# ThermoActuator.net
KiCad netlist of a schematic drawn in EAGLE
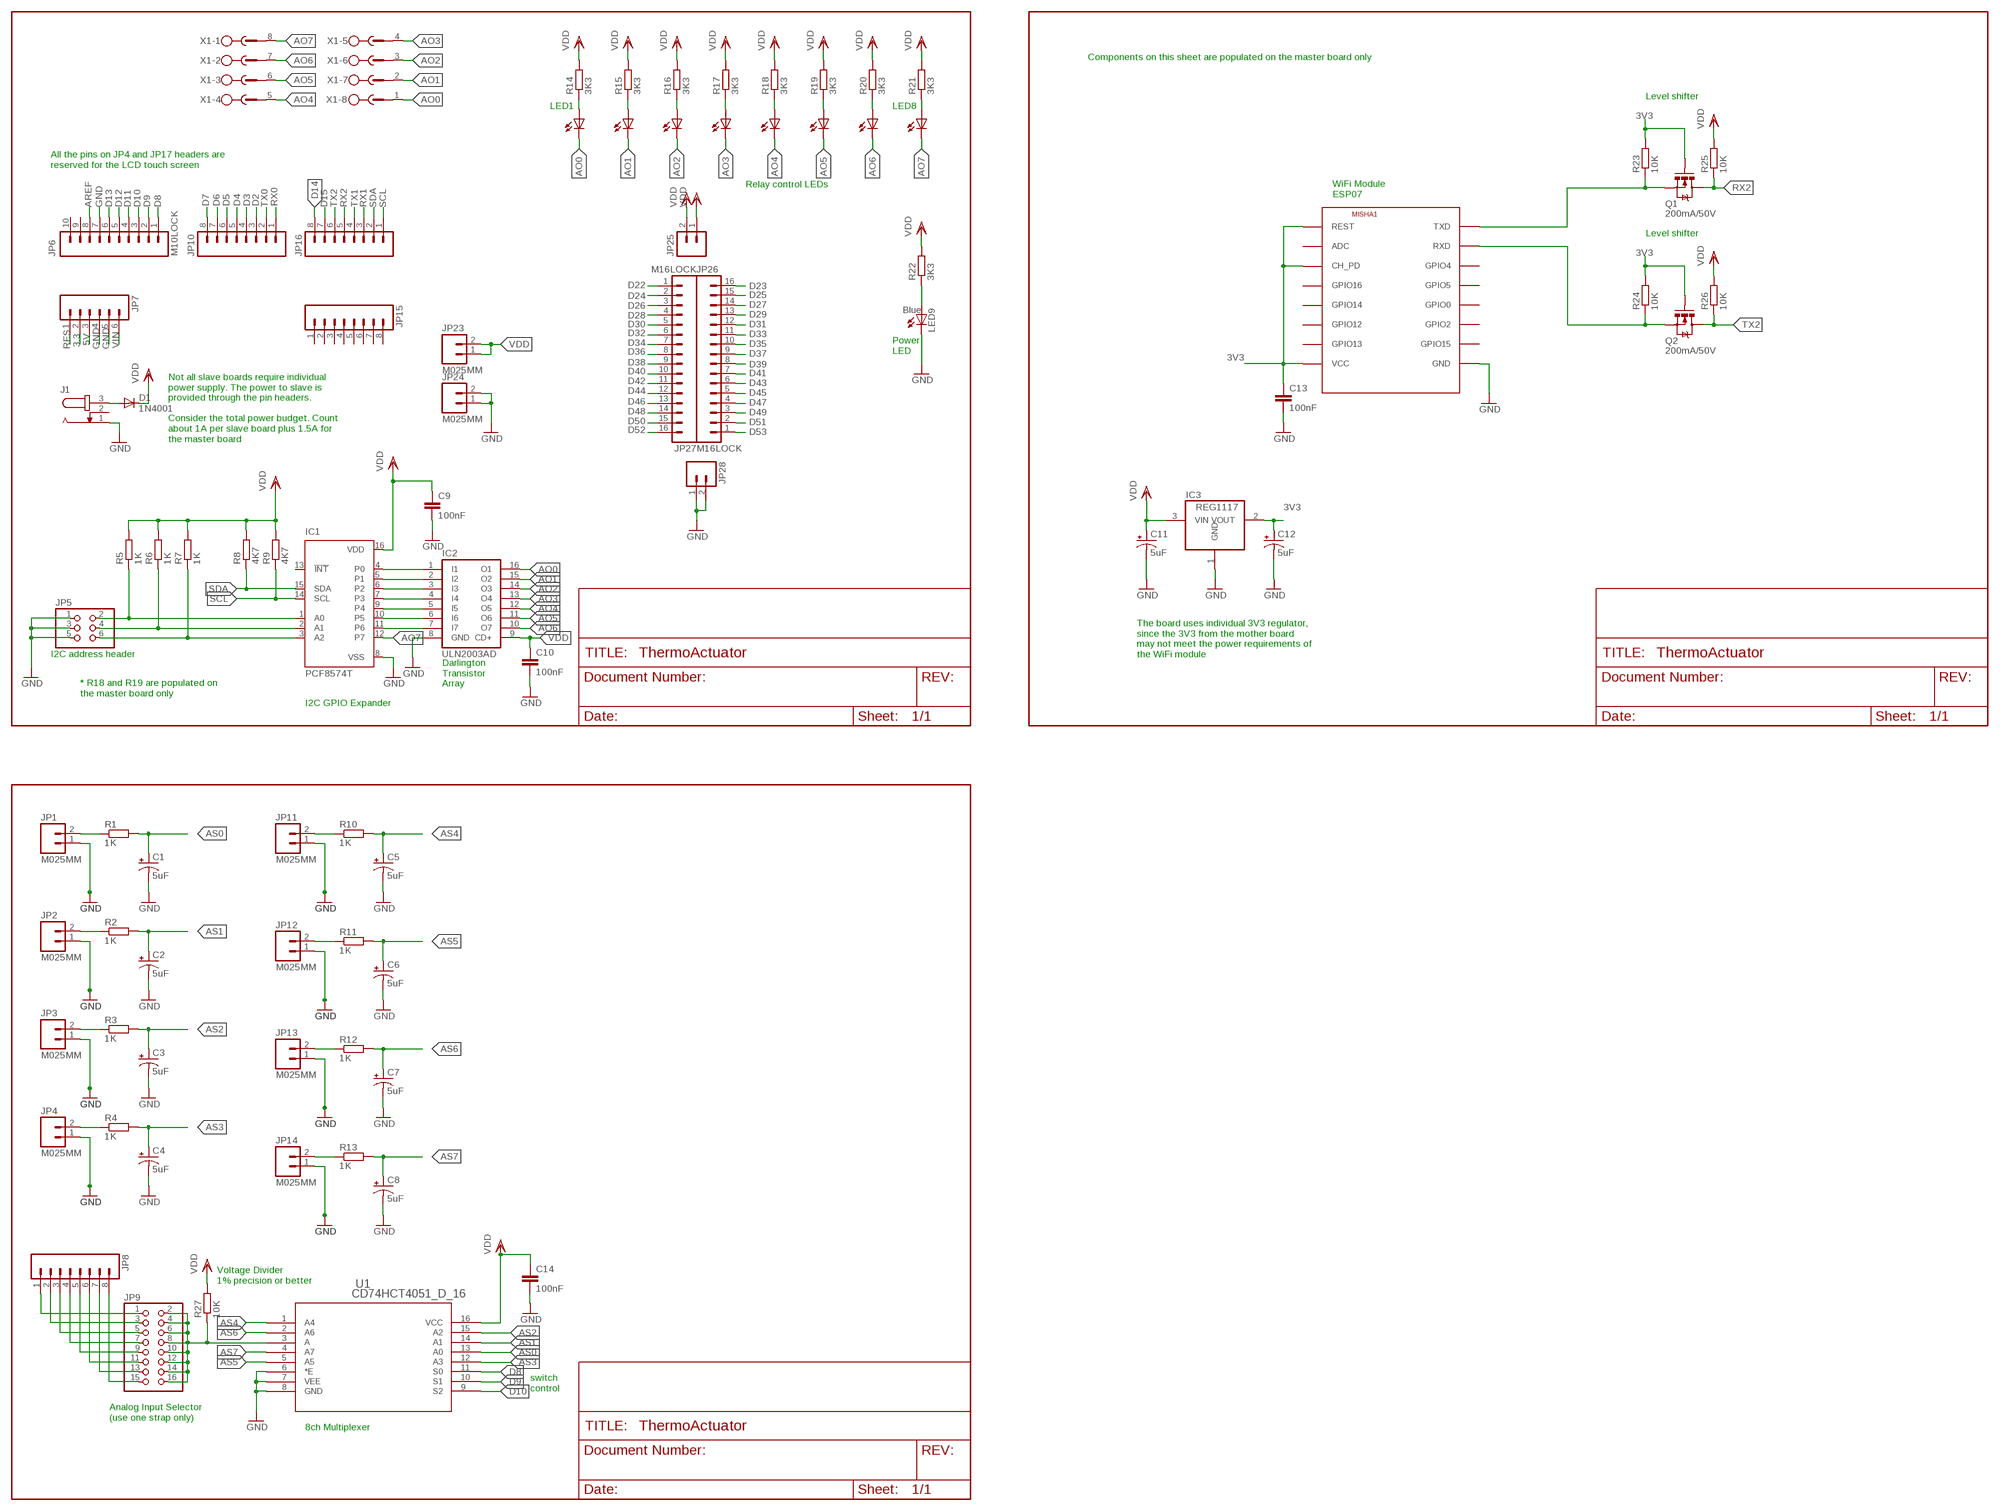
[diagram p0: schematic, sheet 1]

(export (version "E")
  (design (tool "Eeschema 10.0.6"))
  (components
    (comp (ref "1")
      (value "LEDCHIP-LED0805")
      (footprint "eagle-import:CHIP-LED0805")
      (libsource (lib "eagle-import") (part "LEDCHIP-LED0805"))
    )
    (comp (ref "2")
      (value "LEDCHIP-LED0805")
      (footprint "eagle-import:CHIP-LED0805")
      (libsource (lib "eagle-import") (part "LEDCHIP-LED0805"))
    )
    (comp (ref "3")
      (value "LEDCHIP-LED0805")
      (footprint "eagle-import:CHIP-LED0805")
      (libsource (lib "eagle-import") (part "LEDCHIP-LED0805"))
    )
    (comp (ref "4")
      (value "LEDCHIP-LED0805")
      (footprint "eagle-import:CHIP-LED0805")
      (libsource (lib "eagle-import") (part "LEDCHIP-LED0805"))
    )
    (comp (ref "5")
      (value "LEDCHIP-LED0805")
      (footprint "eagle-import:CHIP-LED0805")
      (libsource (lib "eagle-import") (part "LEDCHIP-LED0805"))
    )
    (comp (ref "6")
      (value "LEDCHIP-LED0805")
      (footprint "eagle-import:CHIP-LED0805")
      (libsource (lib "eagle-import") (part "LEDCHIP-LED0805"))
    )
    (comp (ref "7")
      (value "LEDCHIP-LED0805")
      (footprint "eagle-import:CHIP-LED0805")
      (libsource (lib "eagle-import") (part "LEDCHIP-LED0805"))
    )
    (comp (ref "8")
      (value "LEDCHIP-LED0805")
      (footprint "eagle-import:CHIP-LED0805")
      (libsource (lib "eagle-import") (part "LEDCHIP-LED0805"))
    )
    (comp (ref "C1")
      (value "5uF")
      (footprint "eagle-import:EIA3216")
      (libsource (lib "eagle-import") (part "CAP_POL1206"))
    )
    (comp (ref "C2")
      (value "5uF")
      (footprint "eagle-import:EIA3216")
      (libsource (lib "eagle-import") (part "CAP_POL1206"))
    )
    (comp (ref "C3")
      (value "5uF")
      (footprint "eagle-import:EIA3216")
      (libsource (lib "eagle-import") (part "CAP_POL1206"))
    )
    (comp (ref "C4")
      (value "5uF")
      (footprint "eagle-import:EIA3216")
      (libsource (lib "eagle-import") (part "CAP_POL1206"))
    )
    (comp (ref "C5")
      (value "5uF")
      (footprint "eagle-import:EIA3216")
      (libsource (lib "eagle-import") (part "CAP_POL1206"))
    )
    (comp (ref "C6")
      (value "5uF")
      (footprint "eagle-import:EIA3216")
      (libsource (lib "eagle-import") (part "CAP_POL1206"))
    )
    (comp (ref "C7")
      (value "5uF")
      (footprint "eagle-import:EIA3216")
      (libsource (lib "eagle-import") (part "CAP_POL1206"))
    )
    (comp (ref "C8")
      (value "5uF")
      (footprint "eagle-import:EIA3216")
      (libsource (lib "eagle-import") (part "CAP_POL1206"))
    )
    (comp (ref "C9")
      (value "100nF")
      (footprint "eagle-import:C0805")
      (libsource (lib "eagle-import") (part "C-EUC0805"))
    )
    (comp (ref "C10")
      (value "100nF")
      (footprint "eagle-import:C0805")
      (libsource (lib "eagle-import") (part "C-EUC0805"))
    )
    (comp (ref "C11")
      (value "5uF")
      (footprint "eagle-import:EIA3216")
      (libsource (lib "eagle-import") (part "CAP_POL1206"))
    )
    (comp (ref "C12")
      (value "5uF")
      (footprint "eagle-import:EIA3216")
      (libsource (lib "eagle-import") (part "CAP_POL1206"))
    )
    (comp (ref "C13")
      (value "100nF")
      (footprint "eagle-import:C0805")
      (libsource (lib "eagle-import") (part "C-EUC0805"))
    )
    (comp (ref "C14")
      (value "100nF")
      (footprint "eagle-import:C0805")
      (libsource (lib "eagle-import") (part "C-EUC0805"))
    )
    (comp (ref "D1")
      (value "1N4001")
      (footprint "eagle-import:D-10")
      (libsource (lib "eagle-import") (part "DIODE-D-10"))
    )
    (comp (ref "IC1")
      (value "PCF8574T")
      (footprint "eagle-import:SO16W")
      (fields (field (name "MPN") "PCF8574T/3,512"))
      (libsource (lib "eagle-import") (part "PCF8574T"))
    )
    (comp (ref "IC2")
      (value "ULN2003AD")
      (footprint "eagle-import:SO16")
      (libsource (lib "eagle-import") (part "ULN2003AD"))
    )
    (comp (ref "IC3")
      (value "REG1117")
      (footprint "eagle-import:SOT223")
      (libsource (lib "eagle-import") (part "REG1117"))
    )
    (comp (ref "J1")
      (value "JACK-PLUG1")
      (footprint "eagle-import:SPC4078")
      (libsource (lib "eagle-import") (part "JACK-PLUG1"))
    )
    (comp (ref "JP1")
      (value "M025MM")
      (footprint "eagle-import:SCREWTERMINAL-5MM-2")
      (libsource (lib "eagle-import") (part "SparkFun-Connectors_M025MM"))
    )
    (comp (ref "JP2")
      (value "M025MM")
      (footprint "eagle-import:SCREWTERMINAL-5MM-2")
      (libsource (lib "eagle-import") (part "SparkFun-Connectors_M025MM"))
    )
    (comp (ref "JP3")
      (value "M025MM")
      (footprint "eagle-import:SCREWTERMINAL-5MM-2")
      (libsource (lib "eagle-import") (part "SparkFun-Connectors_M025MM"))
    )
    (comp (ref "JP4")
      (value "M025MM")
      (footprint "eagle-import:SCREWTERMINAL-5MM-2")
      (libsource (lib "eagle-import") (part "SparkFun-Connectors_M025MM"))
    )
    (comp (ref "JP5")
      (value "PINHD-2X3")
      (footprint "eagle-import:2X03")
      (libsource (lib "eagle-import") (part "PINHD-2X3"))
    )
    (comp (ref "JP6")
      (value "M10LOCK")
      (footprint "eagle-import:1X10_LOCK")
      (libsource (lib "eagle-import") (part "M10LOCK"))
    )
    (comp (ref "JP7")
      (value "M06LOCK")
      (footprint "eagle-import:1X06_LOCK")
      (libsource (lib "eagle-import") (part "M06LOCK"))
    )
    (comp (ref "JP8")
      (value "M08LOCK")
      (footprint "eagle-import:1X08_LOCK")
      (libsource (lib "eagle-import") (part "M08LOCK"))
    )
    (comp (ref "JP9")
      (value "PINHD-2X8")
      (footprint "eagle-import:2X08")
      (libsource (lib "eagle-import") (part "PINHD-2X8"))
    )
    (comp (ref "JP10")
      (value "M08LOCK")
      (footprint "eagle-import:1X08_LOCK")
      (libsource (lib "eagle-import") (part "M08LOCK"))
    )
    (comp (ref "JP11")
      (value "M025MM")
      (footprint "eagle-import:SCREWTERMINAL-5MM-2")
      (libsource (lib "eagle-import") (part "SparkFun-Connectors_M025MM"))
    )
    (comp (ref "JP12")
      (value "M025MM")
      (footprint "eagle-import:SCREWTERMINAL-5MM-2")
      (libsource (lib "eagle-import") (part "SparkFun-Connectors_M025MM"))
    )
    (comp (ref "JP13")
      (value "M025MM")
      (footprint "eagle-import:SCREWTERMINAL-5MM-2")
      (libsource (lib "eagle-import") (part "SparkFun-Connectors_M025MM"))
    )
    (comp (ref "JP14")
      (value "M025MM")
      (footprint "eagle-import:SCREWTERMINAL-5MM-2")
      (libsource (lib "eagle-import") (part "SparkFun-Connectors_M025MM"))
    )
    (comp (ref "JP15")
      (value "M08LOCK")
      (footprint "eagle-import:1X08_LOCK")
      (libsource (lib "eagle-import") (part "M08LOCK"))
    )
    (comp (ref "JP16")
      (value "M08LOCK")
      (footprint "eagle-import:1X08_LOCK")
      (libsource (lib "eagle-import") (part "M08LOCK"))
    )
    (comp (ref "JP23")
      (value "M025MM")
      (footprint "eagle-import:SCREWTERMINAL-5MM-2")
      (libsource (lib "eagle-import") (part "SparkFun-Connectors_M025MM"))
    )
    (comp (ref "JP24")
      (value "M025MM")
      (footprint "eagle-import:SCREWTERMINAL-5MM-2")
      (libsource (lib "eagle-import") (part "SparkFun-Connectors_M025MM"))
    )
    (comp (ref "JP25")
      (value "M02LOCK")
      (footprint "eagle-import:1X02_LOCK")
      (libsource (lib "eagle-import") (part "M02LOCK"))
    )
    (comp (ref "JP26")
      (value "M16LOCK")
      (footprint "eagle-import:1X16_LOCK")
      (libsource (lib "eagle-import") (part "M16LOCK"))
    )
    (comp (ref "JP27")
      (value "M16LOCK")
      (footprint "eagle-import:1X16_LOCK")
      (libsource (lib "eagle-import") (part "M16LOCK"))
    )
    (comp (ref "JP28")
      (value "M02LOCK")
      (footprint "eagle-import:1X02_LOCK")
      (libsource (lib "eagle-import") (part "M02LOCK"))
    )
    (comp (ref "LED9")
      (value "Blue")
      (footprint "eagle-import:CHIP-LED0805")
      (libsource (lib "eagle-import") (part "LEDCHIP-LED0805"))
    )
    (comp (ref "MISHA1")
      (value "ESP8266-07")
      (footprint "eagle-import:ESP-07")
      (libsource (lib "eagle-import") (part "ESP8266-07"))
    )
    (comp (ref "Q1")
      (value "200mA/50V")
      (footprint "eagle-import:SOT23-3")
      (libsource (lib "eagle-import") (part "MOSFET-NCHANNELBSS138"))
    )
    (comp (ref "Q2")
      (value "200mA/50V")
      (footprint "eagle-import:SOT23-3")
      (libsource (lib "eagle-import") (part "MOSFET-NCHANNELBSS138"))
    )
    (comp (ref "R1")
      (value "1K")
      (footprint "eagle-import:R1206")
      (libsource (lib "eagle-import") (part "R-EU_R1206"))
    )
    (comp (ref "R2")
      (value "1K")
      (footprint "eagle-import:R1206")
      (libsource (lib "eagle-import") (part "R-EU_R1206"))
    )
    (comp (ref "R3")
      (value "1K")
      (footprint "eagle-import:R1206")
      (libsource (lib "eagle-import") (part "R-EU_R1206"))
    )
    (comp (ref "R4")
      (value "1K")
      (footprint "eagle-import:R1206")
      (libsource (lib "eagle-import") (part "R-EU_R1206"))
    )
    (comp (ref "R5")
      (value "1K")
      (footprint "eagle-import:R0805")
      (libsource (lib "eagle-import") (part "R-EU_R0805"))
    )
    (comp (ref "R6")
      (value "1K")
      (footprint "eagle-import:R0805")
      (libsource (lib "eagle-import") (part "R-EU_R0805"))
    )
    (comp (ref "R7")
      (value "1K")
      (footprint "eagle-import:R0805")
      (libsource (lib "eagle-import") (part "R-EU_R0805"))
    )
    (comp (ref "R8")
      (value "4K7")
      (footprint "eagle-import:R0805")
      (libsource (lib "eagle-import") (part "R-EU_R0805"))
    )
    (comp (ref "R9")
      (value "4K7")
      (footprint "eagle-import:R0805")
      (libsource (lib "eagle-import") (part "R-EU_R0805"))
    )
    (comp (ref "R10")
      (value "1K")
      (footprint "eagle-import:R1206")
      (libsource (lib "eagle-import") (part "R-EU_R1206"))
    )
    (comp (ref "R11")
      (value "1K")
      (footprint "eagle-import:R1206")
      (libsource (lib "eagle-import") (part "R-EU_R1206"))
    )
    (comp (ref "R12")
      (value "1K")
      (footprint "eagle-import:R1206")
      (libsource (lib "eagle-import") (part "R-EU_R1206"))
    )
    (comp (ref "R13")
      (value "1K")
      (footprint "eagle-import:R1206")
      (libsource (lib "eagle-import") (part "R-EU_R1206"))
    )
    (comp (ref "R14")
      (value "3K3")
      (footprint "eagle-import:R0805")
      (libsource (lib "eagle-import") (part "R-EU_R0805"))
    )
    (comp (ref "R15")
      (value "3K3")
      (footprint "eagle-import:R0805")
      (libsource (lib "eagle-import") (part "R-EU_R0805"))
    )
    (comp (ref "R16")
      (value "3K3")
      (footprint "eagle-import:R0805")
      (libsource (lib "eagle-import") (part "R-EU_R0805"))
    )
    (comp (ref "R17")
      (value "3K3")
      (footprint "eagle-import:R0805")
      (libsource (lib "eagle-import") (part "R-EU_R0805"))
    )
    (comp (ref "R18")
      (value "3K3")
      (footprint "eagle-import:R0805")
      (libsource (lib "eagle-import") (part "R-EU_R0805"))
    )
    (comp (ref "R19")
      (value "3K3")
      (footprint "eagle-import:R0805")
      (libsource (lib "eagle-import") (part "R-EU_R0805"))
    )
    (comp (ref "R20")
      (value "3K3")
      (footprint "eagle-import:R0805")
      (libsource (lib "eagle-import") (part "R-EU_R0805"))
    )
    (comp (ref "R21")
      (value "3K3")
      (footprint "eagle-import:R0805")
      (libsource (lib "eagle-import") (part "R-EU_R0805"))
    )
    (comp (ref "R22")
      (value "3K3")
      (footprint "eagle-import:R0805")
      (libsource (lib "eagle-import") (part "R-EU_R0805"))
    )
    (comp (ref "R23")
      (value "10K")
      (footprint "eagle-import:R0805")
      (libsource (lib "eagle-import") (part "R-EU_R0805"))
    )
    (comp (ref "R24")
      (value "10K")
      (footprint "eagle-import:R0805")
      (libsource (lib "eagle-import") (part "R-EU_R0805"))
    )
    (comp (ref "R25")
      (value "10K")
      (footprint "eagle-import:R0805")
      (libsource (lib "eagle-import") (part "R-EU_R0805"))
    )
    (comp (ref "R26")
      (value "10K")
      (footprint "eagle-import:R0805")
      (libsource (lib "eagle-import") (part "R-EU_R0805"))
    )
    (comp (ref "R27")
      (value "10K")
      (footprint "eagle-import:R0805")
      (libsource (lib "eagle-import") (part "resistor_R-EU_R0805"))
    )
    (comp (ref "U1")
      (value "CD74HCT4051_D_16")
      (footprint "eagle-import:D16")
      (fields
        (field (name "GENERIC_PART_NUMBER") "CD74HCT4051")
        (field (name "MANUFACTURER") "Texas Instruments")
      )
      (libsource (lib "eagle-import") (part "CD74HCT4051_D_16"))
    )
    (comp (ref "X1")
      (value "MSTBV8")
      (footprint "eagle-import:MSTBV8")
      (libsource (lib "eagle-import") (part "MSTBV8"))
    )
  )
  (nets
    (net (code "1") (name "/3.3") (class "Default")
      (node (ref "JP7") (pin "2") (pinfunction "2_2") (pintype "passive"))
    )
    (net (code "2") (name "/3V3") (class "Default")
      (node (ref "C12") (pin "A") (pinfunction "+_A") (pintype "passive"))
      (node (ref "C13") (pin "1") (pinfunction "1_1") (pintype "passive"))
      (node (ref "IC3") (pin "2") (pinfunction "VOUT_2") (pintype "output"))
      (node (ref "MISHA1") (pin "CH_PD") (pinfunction "CH_PD_CH_PD") (pintype "input"))
      (node (ref "MISHA1") (pin "REST") (pinfunction "REST_REST") (pintype "bidirectional"))
      (node (ref "MISHA1") (pin "VCC") (pinfunction "VCC_VCC") (pintype "power_in"))
      (node (ref "Q1") (pin "1") (pinfunction "G_1") (pintype "passive"))
      (node (ref "Q2") (pin "1") (pinfunction "G_1") (pintype "passive"))
      (node (ref "R23") (pin "2") (pinfunction "2_2") (pintype "passive"))
      (node (ref "R24") (pin "2") (pinfunction "2_2") (pintype "passive"))
    )
    (net (code "3") (name "/5V") (class "Default")
      (node (ref "JP7") (pin "3") (pinfunction "3_3") (pintype "passive"))
    )
    (net (code "4") (name "/AREF") (class "Default")
      (node (ref "JP6") (pin "8") (pinfunction "8_8") (pintype "passive"))
    )
    (net (code "5") (name "/D2") (class "Default")
      (node (ref "JP10") (pin "3") (pinfunction "3_3") (pintype "passive"))
    )
    (net (code "6") (name "/D3") (class "Default")
      (node (ref "JP10") (pin "4") (pinfunction "4_4") (pintype "passive"))
    )
    (net (code "7") (name "/D4") (class "Default")
      (node (ref "JP10") (pin "5") (pinfunction "5_5") (pintype "passive"))
    )
    (net (code "8") (name "/D5") (class "Default")
      (node (ref "JP10") (pin "6") (pinfunction "6_6") (pintype "passive"))
    )
    (net (code "9") (name "/D6") (class "Default")
      (node (ref "JP10") (pin "7") (pinfunction "7_7") (pintype "passive"))
    )
    (net (code "10") (name "/D7") (class "Default")
      (node (ref "JP10") (pin "8") (pinfunction "8_8") (pintype "passive"))
    )
    (net (code "11") (name "/D11") (class "Default")
      (node (ref "JP6") (pin "4") (pinfunction "4_4") (pintype "passive"))
    )
    (net (code "12") (name "/D12") (class "Default")
      (node (ref "JP6") (pin "5") (pinfunction "5_5") (pintype "passive"))
    )
    (net (code "13") (name "/D13") (class "Default")
      (node (ref "JP6") (pin "6") (pinfunction "6_6") (pintype "passive"))
    )
    (net (code "14") (name "/D15") (class "Default")
      (node (ref "JP16") (pin "7") (pinfunction "7_7") (pintype "passive"))
    )
    (net (code "15") (name "/D22") (class "Default")
      (node (ref "JP27") (pin "1") (pinfunction "1_1") (pintype "passive"))
    )
    (net (code "16") (name "/D23") (class "Default")
      (node (ref "JP26") (pin "16") (pinfunction "16_16") (pintype "passive"))
    )
    (net (code "17") (name "/D24") (class "Default")
      (node (ref "JP27") (pin "2") (pinfunction "2_2") (pintype "passive"))
    )
    (net (code "18") (name "/D25") (class "Default")
      (node (ref "JP26") (pin "15") (pinfunction "15_15") (pintype "passive"))
    )
    (net (code "19") (name "/D26") (class "Default")
      (node (ref "JP27") (pin "3") (pinfunction "3_3") (pintype "passive"))
    )
    (net (code "20") (name "/D27") (class "Default")
      (node (ref "JP26") (pin "14") (pinfunction "14_14") (pintype "passive"))
    )
    (net (code "21") (name "/D28") (class "Default")
      (node (ref "JP27") (pin "4") (pinfunction "4_4") (pintype "passive"))
    )
    (net (code "22") (name "/D29") (class "Default")
      (node (ref "JP26") (pin "13") (pinfunction "13_13") (pintype "passive"))
    )
    (net (code "23") (name "/D30") (class "Default")
      (node (ref "JP27") (pin "5") (pinfunction "5_5") (pintype "passive"))
    )
    (net (code "24") (name "/D31") (class "Default")
      (node (ref "JP26") (pin "12") (pinfunction "12_12") (pintype "passive"))
    )
    (net (code "25") (name "/D32") (class "Default")
      (node (ref "JP27") (pin "6") (pinfunction "6_6") (pintype "passive"))
    )
    (net (code "26") (name "/D33") (class "Default")
      (node (ref "JP26") (pin "11") (pinfunction "11_11") (pintype "passive"))
    )
    (net (code "27") (name "/D34") (class "Default")
      (node (ref "JP27") (pin "7") (pinfunction "7_7") (pintype "passive"))
    )
    (net (code "28") (name "/D35") (class "Default")
      (node (ref "JP26") (pin "10") (pinfunction "10_10") (pintype "passive"))
    )
    (net (code "29") (name "/D36") (class "Default")
      (node (ref "JP27") (pin "8") (pinfunction "8_8") (pintype "passive"))
    )
    (net (code "30") (name "/D37") (class "Default")
      (node (ref "JP26") (pin "9") (pinfunction "9_9") (pintype "passive"))
    )
    (net (code "31") (name "/D38") (class "Default")
      (node (ref "JP27") (pin "9") (pinfunction "9_9") (pintype "passive"))
    )
    (net (code "32") (name "/D39") (class "Default")
      (node (ref "JP26") (pin "8") (pinfunction "8_8") (pintype "passive"))
    )
    (net (code "33") (name "/D40") (class "Default")
      (node (ref "JP27") (pin "10") (pinfunction "10_10") (pintype "passive"))
    )
    (net (code "34") (name "/D41") (class "Default")
      (node (ref "JP26") (pin "7") (pinfunction "7_7") (pintype "passive"))
    )
    (net (code "35") (name "/D42") (class "Default")
      (node (ref "JP27") (pin "11") (pinfunction "11_11") (pintype "passive"))
    )
    (net (code "36") (name "/D43") (class "Default")
      (node (ref "JP26") (pin "6") (pinfunction "6_6") (pintype "passive"))
    )
    (net (code "37") (name "/D44") (class "Default")
      (node (ref "JP27") (pin "12") (pinfunction "12_12") (pintype "passive"))
    )
    (net (code "38") (name "/D45") (class "Default")
      (node (ref "JP26") (pin "5") (pinfunction "5_5") (pintype "passive"))
    )
    (net (code "39") (name "/D46") (class "Default")
      (node (ref "JP27") (pin "13") (pinfunction "13_13") (pintype "passive"))
    )
    (net (code "40") (name "/D47") (class "Default")
      (node (ref "JP26") (pin "4") (pinfunction "4_4") (pintype "passive"))
    )
    (net (code "41") (name "/D48") (class "Default")
      (node (ref "JP27") (pin "14") (pinfunction "14_14") (pintype "passive"))
    )
    (net (code "42") (name "/D49") (class "Default")
      (node (ref "JP26") (pin "3") (pinfunction "3_3") (pintype "passive"))
    )
    (net (code "43") (name "/D50") (class "Default")
      (node (ref "JP27") (pin "15") (pinfunction "15_15") (pintype "passive"))
    )
    (net (code "44") (name "/D51") (class "Default")
      (node (ref "JP26") (pin "2") (pinfunction "2_2") (pintype "passive"))
    )
    (net (code "45") (name "/D52") (class "Default")
      (node (ref "JP27") (pin "16") (pinfunction "16_16") (pintype "passive"))
    )
    (net (code "46") (name "/D53") (class "Default")
      (node (ref "JP26") (pin "1") (pinfunction "1_1") (pintype "passive"))
    )
    (net (code "47") (name "/RES") (class "Default")
      (node (ref "JP7") (pin "1") (pinfunction "1_1") (pintype "passive"))
    )
    (net (code "48") (name "/RX0") (class "Default")
      (node (ref "JP10") (pin "1") (pinfunction "1_1") (pintype "passive"))
    )
    (net (code "49") (name "/RX1") (class "Default")
      (node (ref "JP16") (pin "3") (pinfunction "3_3") (pintype "passive"))
    )
    (net (code "50") (name "/TX0") (class "Default")
      (node (ref "JP10") (pin "2") (pinfunction "2_2") (pintype "passive"))
    )
    (net (code "51") (name "/TX1") (class "Default")
      (node (ref "JP16") (pin "4") (pinfunction "4_4") (pintype "passive"))
    )
    (net (code "52") (name "/VIN") (class "Default")
      (node (ref "JP7") (pin "6") (pinfunction "6_6") (pintype "passive"))
    )
    (net (code "53") (name "AO0") (class "Default")
      (node (ref "1") (pin "C") (pinfunction "C_C") (pintype "passive"))
      (node (ref "IC2") (pin "16") (pinfunction "O1_16") (pintype "open_collector"))
      (node (ref "X1") (pin "1") (pinfunction "SK_1") (pintype "passive"))
    )
    (net (code "54") (name "AO1") (class "Default")
      (node (ref "2") (pin "C") (pinfunction "C_C") (pintype "passive"))
      (node (ref "IC2") (pin "15") (pinfunction "O2_15") (pintype "open_collector"))
      (node (ref "X1") (pin "2") (pinfunction "SK_2") (pintype "passive"))
    )
    (net (code "55") (name "AO2") (class "Default")
      (node (ref "3") (pin "C") (pinfunction "C_C") (pintype "passive"))
      (node (ref "IC2") (pin "14") (pinfunction "O3_14") (pintype "open_collector"))
      (node (ref "X1") (pin "3") (pinfunction "SK_3") (pintype "passive"))
    )
    (net (code "56") (name "AO3") (class "Default")
      (node (ref "4") (pin "C") (pinfunction "C_C") (pintype "passive"))
      (node (ref "IC2") (pin "13") (pinfunction "O4_13") (pintype "open_collector"))
      (node (ref "X1") (pin "4") (pinfunction "SK_4") (pintype "passive"))
    )
    (net (code "57") (name "AO4") (class "Default")
      (node (ref "5") (pin "C") (pinfunction "C_C") (pintype "passive"))
      (node (ref "IC2") (pin "12") (pinfunction "O5_12") (pintype "open_collector"))
      (node (ref "X1") (pin "5") (pinfunction "SK_5") (pintype "passive"))
    )
    (net (code "58") (name "AO5") (class "Default")
      (node (ref "6") (pin "C") (pinfunction "C_C") (pintype "passive"))
      (node (ref "IC2") (pin "11") (pinfunction "O6_11") (pintype "open_collector"))
      (node (ref "X1") (pin "6") (pinfunction "SK_6") (pintype "passive"))
    )
    (net (code "59") (name "AO6") (class "Default")
      (node (ref "7") (pin "C") (pinfunction "C_C") (pintype "passive"))
      (node (ref "IC2") (pin "10") (pinfunction "O7_10") (pintype "open_collector"))
      (node (ref "X1") (pin "7") (pinfunction "SK_7") (pintype "passive"))
    )
    (net (code "60") (name "AO7") (class "Default")
      (node (ref "8") (pin "C") (pinfunction "C_C") (pintype "passive"))
      (node (ref "IC1") (pin "12") (pinfunction "P7_12") (pintype "bidirectional"))
      (node (ref "X1") (pin "8") (pinfunction "SK_8") (pintype "passive"))
    )
    (net (code "61") (name "AS0") (class "Default")
      (node (ref "C1") (pin "A") (pinfunction "+_A") (pintype "passive"))
      (node (ref "R1") (pin "2") (pinfunction "2_2") (pintype "passive"))
      (node (ref "U1") (pin "13") (pinfunction "A0_13") (pintype "bidirectional"))
    )
    (net (code "62") (name "AS1") (class "Default")
      (node (ref "C2") (pin "A") (pinfunction "+_A") (pintype "passive"))
      (node (ref "R2") (pin "2") (pinfunction "2_2") (pintype "passive"))
      (node (ref "U1") (pin "14") (pinfunction "A1_14") (pintype "bidirectional"))
    )
    (net (code "63") (name "AS2") (class "Default")
      (node (ref "C3") (pin "A") (pinfunction "+_A") (pintype "passive"))
      (node (ref "R3") (pin "2") (pinfunction "2_2") (pintype "passive"))
      (node (ref "U1") (pin "15") (pinfunction "A2_15") (pintype "bidirectional"))
    )
    (net (code "64") (name "AS3") (class "Default")
      (node (ref "C4") (pin "A") (pinfunction "+_A") (pintype "passive"))
      (node (ref "R4") (pin "2") (pinfunction "2_2") (pintype "passive"))
      (node (ref "U1") (pin "12") (pinfunction "A3_12") (pintype "bidirectional"))
    )
    (net (code "65") (name "AS4") (class "Default")
      (node (ref "C5") (pin "A") (pinfunction "+_A") (pintype "passive"))
      (node (ref "R10") (pin "2") (pinfunction "2_2") (pintype "passive"))
      (node (ref "U1") (pin "1") (pinfunction "A4_1") (pintype "bidirectional"))
    )
    (net (code "66") (name "AS5") (class "Default")
      (node (ref "C6") (pin "A") (pinfunction "+_A") (pintype "passive"))
      (node (ref "R11") (pin "2") (pinfunction "2_2") (pintype "passive"))
      (node (ref "U1") (pin "5") (pinfunction "A5_5") (pintype "bidirectional"))
    )
    (net (code "67") (name "AS6") (class "Default")
      (node (ref "C7") (pin "A") (pinfunction "+_A") (pintype "passive"))
      (node (ref "R12") (pin "2") (pinfunction "2_2") (pintype "passive"))
      (node (ref "U1") (pin "2") (pinfunction "A6_2") (pintype "bidirectional"))
    )
    (net (code "68") (name "AS7") (class "Default")
      (node (ref "C8") (pin "A") (pinfunction "+_A") (pintype "passive"))
      (node (ref "R13") (pin "2") (pinfunction "2_2") (pintype "passive"))
      (node (ref "U1") (pin "4") (pinfunction "A7_4") (pintype "bidirectional"))
    )
    (net (code "69") (name "D8") (class "Default")
      (node (ref "JP6") (pin "1") (pinfunction "1_1") (pintype "passive"))
      (node (ref "U1") (pin "11") (pinfunction "S0_11") (pintype "output"))
    )
    (net (code "70") (name "D9") (class "Default")
      (node (ref "JP6") (pin "2") (pinfunction "2_2") (pintype "passive"))
      (node (ref "U1") (pin "10") (pinfunction "S1_10") (pintype "output"))
    )
    (net (code "71") (name "D10") (class "Default")
      (node (ref "JP6") (pin "3") (pinfunction "3_3") (pintype "passive"))
      (node (ref "U1") (pin "9") (pinfunction "S2_9") (pintype "output"))
    )
    (net (code "72") (name "D14") (class "Default")
      (node (ref "JP16") (pin "8") (pinfunction "8_8") (pintype "passive"))
    )
    (net (code "73") (name "GND") (class "Default")
      (node (ref "C1") (pin "C") (pinfunction "-_C") (pintype "passive"))
      (node (ref "C10") (pin "2") (pinfunction "2_2") (pintype "passive"))
      (node (ref "C11") (pin "C") (pinfunction "-_C") (pintype "passive"))
      (node (ref "C12") (pin "C") (pinfunction "-_C") (pintype "passive"))
      (node (ref "C13") (pin "2") (pinfunction "2_2") (pintype "passive"))
      (node (ref "C14") (pin "2") (pinfunction "2_2") (pintype "passive"))
      (node (ref "C2") (pin "C") (pinfunction "-_C") (pintype "passive"))
      (node (ref "C3") (pin "C") (pinfunction "-_C") (pintype "passive"))
      (node (ref "C4") (pin "C") (pinfunction "-_C") (pintype "passive"))
      (node (ref "C5") (pin "C") (pinfunction "-_C") (pintype "passive"))
      (node (ref "C6") (pin "C") (pinfunction "-_C") (pintype "passive"))
      (node (ref "C7") (pin "C") (pinfunction "-_C") (pintype "passive"))
      (node (ref "C8") (pin "C") (pinfunction "-_C") (pintype "passive"))
      (node (ref "C9") (pin "2") (pinfunction "2_2") (pintype "passive"))
      (node (ref "IC1") (pin "8") (pinfunction "VSS_8") (pintype "power_in"))
      (node (ref "IC2") (pin "8") (pinfunction "GND_8") (pintype "power_in"))
      (node (ref "IC3") (pin "1") (pinfunction "GND_1") (pintype "power_in"))
      (node (ref "J1") (pin "1") (pinfunction "1_1") (pintype "passive"))
      (node (ref "JP1") (pin "1") (pinfunction "1_1") (pintype "passive"))
      (node (ref "JP11") (pin "1") (pinfunction "1_1") (pintype "passive"))
      (node (ref "JP12") (pin "1") (pinfunction "1_1") (pintype "passive"))
      (node (ref "JP13") (pin "1") (pinfunction "1_1") (pintype "passive"))
      (node (ref "JP14") (pin "1") (pinfunction "1_1") (pintype "passive"))
      (node (ref "JP2") (pin "1") (pinfunction "1_1") (pintype "passive"))
      (node (ref "JP24") (pin "1") (pinfunction "1_1") (pintype "passive"))
      (node (ref "JP24") (pin "2") (pinfunction "2_2") (pintype "passive"))
      (node (ref "JP28") (pin "1") (pinfunction "1_1") (pintype "passive"))
      (node (ref "JP28") (pin "2") (pinfunction "2_2") (pintype "passive"))
      (node (ref "JP3") (pin "1") (pinfunction "1_1") (pintype "passive"))
      (node (ref "JP4") (pin "1") (pinfunction "1_1") (pintype "passive"))
      (node (ref "JP5") (pin "1") (pinfunction "1_1") (pintype "passive"))
      (node (ref "JP5") (pin "3") (pinfunction "3_3") (pintype "passive"))
      (node (ref "JP5") (pin "5") (pinfunction "5_5") (pintype "passive"))
      (node (ref "JP6") (pin "7") (pinfunction "7_7") (pintype "passive"))
      (node (ref "JP7") (pin "4") (pinfunction "4_4") (pintype "passive"))
      (node (ref "JP7") (pin "5") (pinfunction "5_5") (pintype "passive"))
      (node (ref "LED9") (pin "C") (pinfunction "C_C") (pintype "passive"))
      (node (ref "MISHA1") (pin "GND") (pinfunction "GND_GND") (pintype "power_in"))
      (node (ref "U1") (pin "6") (pinfunction "*E_6") (pintype "input"))
      (node (ref "U1") (pin "7") (pinfunction "VEE_7") (pintype "power_in"))
      (node (ref "U1") (pin "8") (pinfunction "GND_8") (pintype "power_in"))
    )
    (net (code "74") (name "Net-(1-PadA)") (class "Default")
      (node (ref "1") (pin "A") (pinfunction "A_A") (pintype "passive"))
      (node (ref "R14") (pin "1") (pinfunction "1_1") (pintype "passive"))
    )
    (net (code "75") (name "Net-(2-PadA)") (class "Default")
      (node (ref "2") (pin "A") (pinfunction "A_A") (pintype "passive"))
      (node (ref "R15") (pin "1") (pinfunction "1_1") (pintype "passive"))
    )
    (net (code "76") (name "Net-(3-PadA)") (class "Default")
      (node (ref "3") (pin "A") (pinfunction "A_A") (pintype "passive"))
      (node (ref "R16") (pin "1") (pinfunction "1_1") (pintype "passive"))
    )
    (net (code "77") (name "Net-(4-PadA)") (class "Default")
      (node (ref "4") (pin "A") (pinfunction "A_A") (pintype "passive"))
      (node (ref "R17") (pin "1") (pinfunction "1_1") (pintype "passive"))
    )
    (net (code "78") (name "Net-(5-PadA)") (class "Default")
      (node (ref "5") (pin "A") (pinfunction "A_A") (pintype "passive"))
      (node (ref "R18") (pin "1") (pinfunction "1_1") (pintype "passive"))
    )
    (net (code "79") (name "Net-(6-PadA)") (class "Default")
      (node (ref "6") (pin "A") (pinfunction "A_A") (pintype "passive"))
      (node (ref "R19") (pin "1") (pinfunction "1_1") (pintype "passive"))
    )
    (net (code "80") (name "Net-(7-PadA)") (class "Default")
      (node (ref "7") (pin "A") (pinfunction "A_A") (pintype "passive"))
      (node (ref "R20") (pin "1") (pinfunction "1_1") (pintype "passive"))
    )
    (net (code "81") (name "Net-(8-PadA)") (class "Default")
      (node (ref "8") (pin "A") (pinfunction "A_A") (pintype "passive"))
      (node (ref "R21") (pin "1") (pinfunction "1_1") (pintype "passive"))
    )
    (net (code "82") (name "Net-(D1-PadA)") (class "Default")
      (node (ref "D1") (pin "A") (pinfunction "A_A") (pintype "passive"))
      (node (ref "J1") (pin "3") (pinfunction "3_3") (pintype "passive"))
    )
    (net (code "83") (name "Net-(IC1-A0)") (class "Default")
      (node (ref "IC1") (pin "1") (pinfunction "A0_1") (pintype "input"))
      (node (ref "JP5") (pin "2") (pinfunction "2_2") (pintype "passive"))
      (node (ref "R5") (pin "1") (pinfunction "1_1") (pintype "passive"))
    )
    (net (code "84") (name "Net-(IC1-A1)") (class "Default")
      (node (ref "IC1") (pin "2") (pinfunction "A1_2") (pintype "input"))
      (node (ref "JP5") (pin "4") (pinfunction "4_4") (pintype "passive"))
      (node (ref "R6") (pin "1") (pinfunction "1_1") (pintype "passive"))
    )
    (net (code "85") (name "Net-(IC1-A2)") (class "Default")
      (node (ref "IC1") (pin "3") (pinfunction "A2_3") (pintype "input"))
      (node (ref "JP5") (pin "6") (pinfunction "6_6") (pintype "passive"))
      (node (ref "R7") (pin "1") (pinfunction "1_1") (pintype "passive"))
    )
    (net (code "86") (name "Net-(IC1-P0)") (class "Default")
      (node (ref "IC1") (pin "4") (pinfunction "P0_4") (pintype "bidirectional"))
      (node (ref "IC2") (pin "1") (pinfunction "I1_1") (pintype "input"))
    )
    (net (code "87") (name "Net-(IC1-P1)") (class "Default")
      (node (ref "IC1") (pin "5") (pinfunction "P1_5") (pintype "bidirectional"))
      (node (ref "IC2") (pin "2") (pinfunction "I2_2") (pintype "input"))
    )
    (net (code "88") (name "Net-(IC1-P2)") (class "Default")
      (node (ref "IC1") (pin "6") (pinfunction "P2_6") (pintype "bidirectional"))
      (node (ref "IC2") (pin "3") (pinfunction "I3_3") (pintype "input"))
    )
    (net (code "89") (name "Net-(IC1-P3)") (class "Default")
      (node (ref "IC1") (pin "7") (pinfunction "P3_7") (pintype "bidirectional"))
      (node (ref "IC2") (pin "4") (pinfunction "I4_4") (pintype "input"))
    )
    (net (code "90") (name "Net-(IC1-P4)") (class "Default")
      (node (ref "IC1") (pin "9") (pinfunction "P4_9") (pintype "bidirectional"))
      (node (ref "IC2") (pin "5") (pinfunction "I5_5") (pintype "input"))
    )
    (net (code "91") (name "Net-(IC1-P5)") (class "Default")
      (node (ref "IC1") (pin "10") (pinfunction "P5_10") (pintype "bidirectional"))
      (node (ref "IC2") (pin "6") (pinfunction "I6_6") (pintype "input"))
    )
    (net (code "92") (name "Net-(IC1-P6)") (class "Default")
      (node (ref "IC1") (pin "11") (pinfunction "P6_11") (pintype "bidirectional"))
      (node (ref "IC2") (pin "7") (pinfunction "I7_7") (pintype "input"))
    )
    (net (code "93") (name "Net-(JP1-Pad2)") (class "Default")
      (node (ref "JP1") (pin "2") (pinfunction "2_2") (pintype "passive"))
      (node (ref "R1") (pin "1") (pinfunction "1_1") (pintype "passive"))
    )
    (net (code "94") (name "Net-(JP2-Pad2)") (class "Default")
      (node (ref "JP2") (pin "2") (pinfunction "2_2") (pintype "passive"))
      (node (ref "R2") (pin "1") (pinfunction "1_1") (pintype "passive"))
    )
    (net (code "95") (name "Net-(JP3-Pad2)") (class "Default")
      (node (ref "JP3") (pin "2") (pinfunction "2_2") (pintype "passive"))
      (node (ref "R3") (pin "1") (pinfunction "1_1") (pintype "passive"))
    )
    (net (code "96") (name "Net-(JP4-Pad2)") (class "Default")
      (node (ref "JP4") (pin "2") (pinfunction "2_2") (pintype "passive"))
      (node (ref "R4") (pin "1") (pinfunction "1_1") (pintype "passive"))
    )
    (net (code "97") (name "Net-(JP8-Pad1)") (class "Default")
      (node (ref "JP8") (pin "1") (pinfunction "1_1") (pintype "passive"))
      (node (ref "JP9") (pin "1") (pinfunction "1_1") (pintype "passive"))
    )
    (net (code "98") (name "Net-(JP8-Pad2)") (class "Default")
      (node (ref "JP8") (pin "2") (pinfunction "2_2") (pintype "passive"))
      (node (ref "JP9") (pin "3") (pinfunction "3_3") (pintype "passive"))
    )
    (net (code "99") (name "Net-(JP8-Pad3)") (class "Default")
      (node (ref "JP8") (pin "3") (pinfunction "3_3") (pintype "passive"))
      (node (ref "JP9") (pin "5") (pinfunction "5_5") (pintype "passive"))
    )
    (net (code "100") (name "Net-(JP8-Pad4)") (class "Default")
      (node (ref "JP8") (pin "4") (pinfunction "4_4") (pintype "passive"))
      (node (ref "JP9") (pin "7") (pinfunction "7_7") (pintype "passive"))
    )
    (net (code "101") (name "Net-(JP8-Pad5)") (class "Default")
      (node (ref "JP8") (pin "5") (pinfunction "5_5") (pintype "passive"))
      (node (ref "JP9") (pin "9") (pinfunction "9_9") (pintype "passive"))
    )
    (net (code "102") (name "Net-(JP8-Pad6)") (class "Default")
      (node (ref "JP8") (pin "6") (pinfunction "6_6") (pintype "passive"))
      (node (ref "JP9") (pin "11") (pinfunction "11_11") (pintype "passive"))
    )
    (net (code "103") (name "Net-(JP8-Pad7)") (class "Default")
      (node (ref "JP8") (pin "7") (pinfunction "7_7") (pintype "passive"))
      (node (ref "JP9") (pin "13") (pinfunction "13_13") (pintype "passive"))
    )
    (net (code "104") (name "Net-(JP8-Pad8)") (class "Default")
      (node (ref "JP8") (pin "8") (pinfunction "8_8") (pintype "passive"))
      (node (ref "JP9") (pin "15") (pinfunction "15_15") (pintype "passive"))
    )
    (net (code "105") (name "Net-(JP11-Pad2)") (class "Default")
      (node (ref "JP11") (pin "2") (pinfunction "2_2") (pintype "passive"))
      (node (ref "R10") (pin "1") (pinfunction "1_1") (pintype "passive"))
    )
    (net (code "106") (name "Net-(JP12-Pad2)") (class "Default")
      (node (ref "JP12") (pin "2") (pinfunction "2_2") (pintype "passive"))
      (node (ref "R11") (pin "1") (pinfunction "1_1") (pintype "passive"))
    )
    (net (code "107") (name "Net-(JP13-Pad2)") (class "Default")
      (node (ref "JP13") (pin "2") (pinfunction "2_2") (pintype "passive"))
      (node (ref "R12") (pin "1") (pinfunction "1_1") (pintype "passive"))
    )
    (net (code "108") (name "Net-(JP14-Pad2)") (class "Default")
      (node (ref "JP14") (pin "2") (pinfunction "2_2") (pintype "passive"))
      (node (ref "R13") (pin "1") (pinfunction "1_1") (pintype "passive"))
    )
    (net (code "109") (name "Net-(LED9-PadA)") (class "Default")
      (node (ref "LED9") (pin "A") (pinfunction "A_A") (pintype "passive"))
      (node (ref "R22") (pin "1") (pinfunction "1_1") (pintype "passive"))
    )
    (net (code "110") (name "Net-(Q1-S)") (class "Default")
      (node (ref "MISHA1") (pin "TXD") (pinfunction "TXD_TXD") (pintype "output"))
      (node (ref "Q1") (pin "2") (pinfunction "S_2") (pintype "passive"))
      (node (ref "R23") (pin "1") (pinfunction "1_1") (pintype "passive"))
    )
    (net (code "111") (name "Net-(Q2-S)") (class "Default")
      (node (ref "MISHA1") (pin "RXD") (pinfunction "RXD_RXD") (pintype "input"))
      (node (ref "Q2") (pin "2") (pinfunction "S_2") (pintype "passive"))
      (node (ref "R24") (pin "1") (pinfunction "1_1") (pintype "passive"))
    )
    (net (code "112") (name "Net-(U1-A)") (class "Default")
      (node (ref "JP9") (pin "10") (pinfunction "10_10") (pintype "passive"))
      (node (ref "JP9") (pin "12") (pinfunction "12_12") (pintype "passive"))
      (node (ref "JP9") (pin "14") (pinfunction "14_14") (pintype "passive"))
      (node (ref "JP9") (pin "16") (pinfunction "16_16") (pintype "passive"))
      (node (ref "JP9") (pin "2") (pinfunction "2_2") (pintype "passive"))
      (node (ref "JP9") (pin "4") (pinfunction "4_4") (pintype "passive"))
      (node (ref "JP9") (pin "6") (pinfunction "6_6") (pintype "passive"))
      (node (ref "JP9") (pin "8") (pinfunction "8_8") (pintype "passive"))
      (node (ref "R27") (pin "1") (pinfunction "1_1") (pintype "passive"))
      (node (ref "U1") (pin "3") (pinfunction "A_3") (pintype "bidirectional"))
    )
    (net (code "113") (name "RX2") (class "Default")
      (node (ref "JP16") (pin "5") (pinfunction "5_5") (pintype "passive"))
      (node (ref "Q1") (pin "3") (pinfunction "D_3") (pintype "passive"))
      (node (ref "R25") (pin "1") (pinfunction "1_1") (pintype "passive"))
    )
    (net (code "114") (name "SCL") (class "Default")
      (node (ref "IC1") (pin "14") (pinfunction "SCL_14") (pintype "input"))
      (node (ref "JP16") (pin "1") (pinfunction "1_1") (pintype "passive"))
      (node (ref "R9") (pin "1") (pinfunction "1_1") (pintype "passive"))
    )
    (net (code "115") (name "SDA") (class "Default")
      (node (ref "IC1") (pin "15") (pinfunction "SDA_15") (pintype "bidirectional"))
      (node (ref "JP16") (pin "2") (pinfunction "2_2") (pintype "passive"))
      (node (ref "R8") (pin "1") (pinfunction "1_1") (pintype "passive"))
    )
    (net (code "116") (name "TX2") (class "Default")
      (node (ref "JP16") (pin "6") (pinfunction "6_6") (pintype "passive"))
      (node (ref "Q2") (pin "3") (pinfunction "D_3") (pintype "passive"))
      (node (ref "R26") (pin "1") (pinfunction "1_1") (pintype "passive"))
    )
    (net (code "117") (name "VDD") (class "Default")
      (node (ref "C10") (pin "1") (pinfunction "1_1") (pintype "passive"))
      (node (ref "C11") (pin "A") (pinfunction "+_A") (pintype "passive"))
      (node (ref "C14") (pin "1") (pinfunction "1_1") (pintype "passive"))
      (node (ref "C9") (pin "1") (pinfunction "1_1") (pintype "passive"))
      (node (ref "D1") (pin "C") (pinfunction "C_C") (pintype "passive"))
      (node (ref "IC1") (pin "16") (pinfunction "VDD_16") (pintype "power_in"))
      (node (ref "IC2") (pin "9") (pinfunction "CD+_9") (pintype "passive"))
      (node (ref "IC3") (pin "3") (pinfunction "VIN_3") (pintype "input"))
      (node (ref "JP23") (pin "1") (pinfunction "1_1") (pintype "passive"))
      (node (ref "JP23") (pin "2") (pinfunction "2_2") (pintype "passive"))
      (node (ref "JP25") (pin "1") (pinfunction "1_1") (pintype "passive"))
      (node (ref "JP25") (pin "2") (pinfunction "2_2") (pintype "passive"))
      (node (ref "R14") (pin "2") (pinfunction "2_2") (pintype "passive"))
      (node (ref "R15") (pin "2") (pinfunction "2_2") (pintype "passive"))
      (node (ref "R16") (pin "2") (pinfunction "2_2") (pintype "passive"))
      (node (ref "R17") (pin "2") (pinfunction "2_2") (pintype "passive"))
      (node (ref "R18") (pin "2") (pinfunction "2_2") (pintype "passive"))
      (node (ref "R19") (pin "2") (pinfunction "2_2") (pintype "passive"))
      (node (ref "R20") (pin "2") (pinfunction "2_2") (pintype "passive"))
      (node (ref "R21") (pin "2") (pinfunction "2_2") (pintype "passive"))
      (node (ref "R22") (pin "2") (pinfunction "2_2") (pintype "passive"))
      (node (ref "R25") (pin "2") (pinfunction "2_2") (pintype "passive"))
      (node (ref "R26") (pin "2") (pinfunction "2_2") (pintype "passive"))
      (node (ref "R27") (pin "2") (pinfunction "2_2") (pintype "passive"))
      (node (ref "R5") (pin "2") (pinfunction "2_2") (pintype "passive"))
      (node (ref "R6") (pin "2") (pinfunction "2_2") (pintype "passive"))
      (node (ref "R7") (pin "2") (pinfunction "2_2") (pintype "passive"))
      (node (ref "R8") (pin "2") (pinfunction "2_2") (pintype "passive"))
      (node (ref "R9") (pin "2") (pinfunction "2_2") (pintype "passive"))
      (node (ref "U1") (pin "16") (pinfunction "VCC_16") (pintype "power_in"))
    )
    (net (code "118") (name "unconnected-(IC1-~{INT}-Pad13)") (class "Default")
      (node (ref "IC1") (pin "13") (pinfunction "~{INT}_13") (pintype "output"))
    )
    (net (code "119") (name "unconnected-(J1-Pad2)") (class "Default")
      (node (ref "J1") (pin "2") (pinfunction "2_2") (pintype "passive"))
    )
    (net (code "120") (name "unconnected-(JP6-Pad9)") (class "Default")
      (node (ref "JP6") (pin "9") (pinfunction "9_9") (pintype "passive"))
    )
    (net (code "121") (name "unconnected-(JP6-Pad10)") (class "Default")
      (node (ref "JP6") (pin "10") (pinfunction "10_10") (pintype "passive"))
    )
    (net (code "122") (name "unconnected-(JP15-Pad1)") (class "Default")
      (node (ref "JP15") (pin "1") (pinfunction "1_1") (pintype "passive"))
    )
    (net (code "123") (name "unconnected-(JP15-Pad2)") (class "Default")
      (node (ref "JP15") (pin "2") (pinfunction "2_2") (pintype "passive"))
    )
    (net (code "124") (name "unconnected-(JP15-Pad3)") (class "Default")
      (node (ref "JP15") (pin "3") (pinfunction "3_3") (pintype "passive"))
    )
    (net (code "125") (name "unconnected-(JP15-Pad4)") (class "Default")
      (node (ref "JP15") (pin "4") (pinfunction "4_4") (pintype "passive"))
    )
    (net (code "126") (name "unconnected-(JP15-Pad5)") (class "Default")
      (node (ref "JP15") (pin "5") (pinfunction "5_5") (pintype "passive"))
    )
    (net (code "127") (name "unconnected-(JP15-Pad6)") (class "Default")
      (node (ref "JP15") (pin "6") (pinfunction "6_6") (pintype "passive"))
    )
    (net (code "128") (name "unconnected-(JP15-Pad7)") (class "Default")
      (node (ref "JP15") (pin "7") (pinfunction "7_7") (pintype "passive"))
    )
    (net (code "129") (name "unconnected-(JP15-Pad8)") (class "Default")
      (node (ref "JP15") (pin "8") (pinfunction "8_8") (pintype "passive"))
    )
    (net (code "130") (name "unconnected-(MISHA1-PadADC)") (class "Default")
      (node (ref "MISHA1") (pin "ADC") (pinfunction "ADC_ADC") (pintype "bidirectional"))
    )
    (net (code "131") (name "unconnected-(MISHA1-PadGPIO0)") (class "Default")
      (node (ref "MISHA1") (pin "GPIO0") (pinfunction "GPIO0_GPIO0") (pintype "bidirectional"))
    )
    (net (code "132") (name "unconnected-(MISHA1-PadGPIO2)") (class "Default")
      (node (ref "MISHA1") (pin "GPIO2") (pinfunction "GPIO2_GPIO2") (pintype "bidirectional"))
    )
    (net (code "133") (name "unconnected-(MISHA1-PadGPIO4)") (class "Default")
      (node (ref "MISHA1") (pin "GPIO4") (pinfunction "GPIO4_GPIO4") (pintype "bidirectional"))
    )
    (net (code "134") (name "unconnected-(MISHA1-PadGPIO5)") (class "Default")
      (node (ref "MISHA1") (pin "GPIO5") (pinfunction "GPIO5_GPIO5") (pintype "bidirectional"))
    )
    (net (code "135") (name "unconnected-(MISHA1-PadGPIO12)") (class "Default")
      (node (ref "MISHA1") (pin "GPIO12") (pinfunction "GPIO12_GPIO12") (pintype "bidirectional"))
    )
    (net (code "136") (name "unconnected-(MISHA1-PadGPIO13)") (class "Default")
      (node (ref "MISHA1") (pin "GPIO13") (pinfunction "GPIO13_GPIO13") (pintype "bidirectional"))
    )
    (net (code "137") (name "unconnected-(MISHA1-PadGPIO14)") (class "Default")
      (node (ref "MISHA1") (pin "GPIO14") (pinfunction "GPIO14_GPIO14") (pintype "bidirectional"))
    )
    (net (code "138") (name "unconnected-(MISHA1-PadGPIO15)") (class "Default")
      (node (ref "MISHA1") (pin "GPIO15") (pinfunction "GPIO15_GPIO15") (pintype "input"))
    )
    (net (code "139") (name "unconnected-(MISHA1-PadGPIO16)") (class "Default")
      (node (ref "MISHA1") (pin "GPIO16") (pinfunction "GPIO16_GPIO16") (pintype "bidirectional"))
    )
  )
)
